# Main.net
KiCad netlist of a schematic drawn in Altium Designer
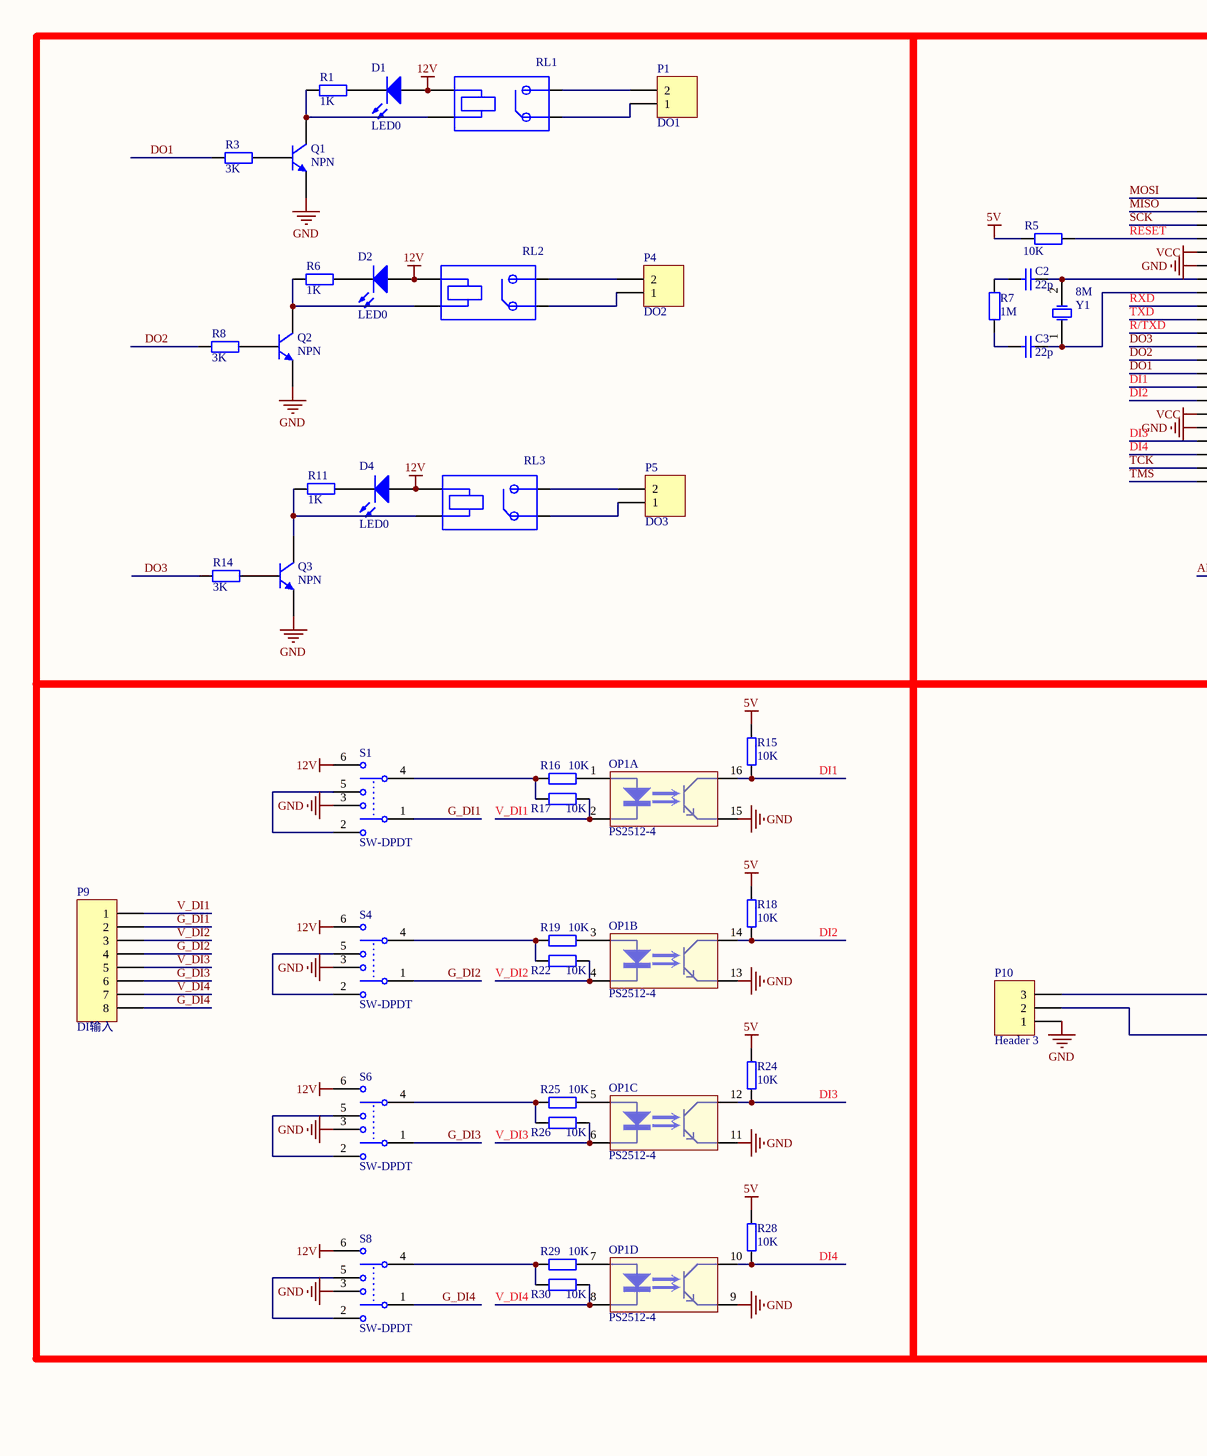
[diagram p0: Main.SchDoc, left]
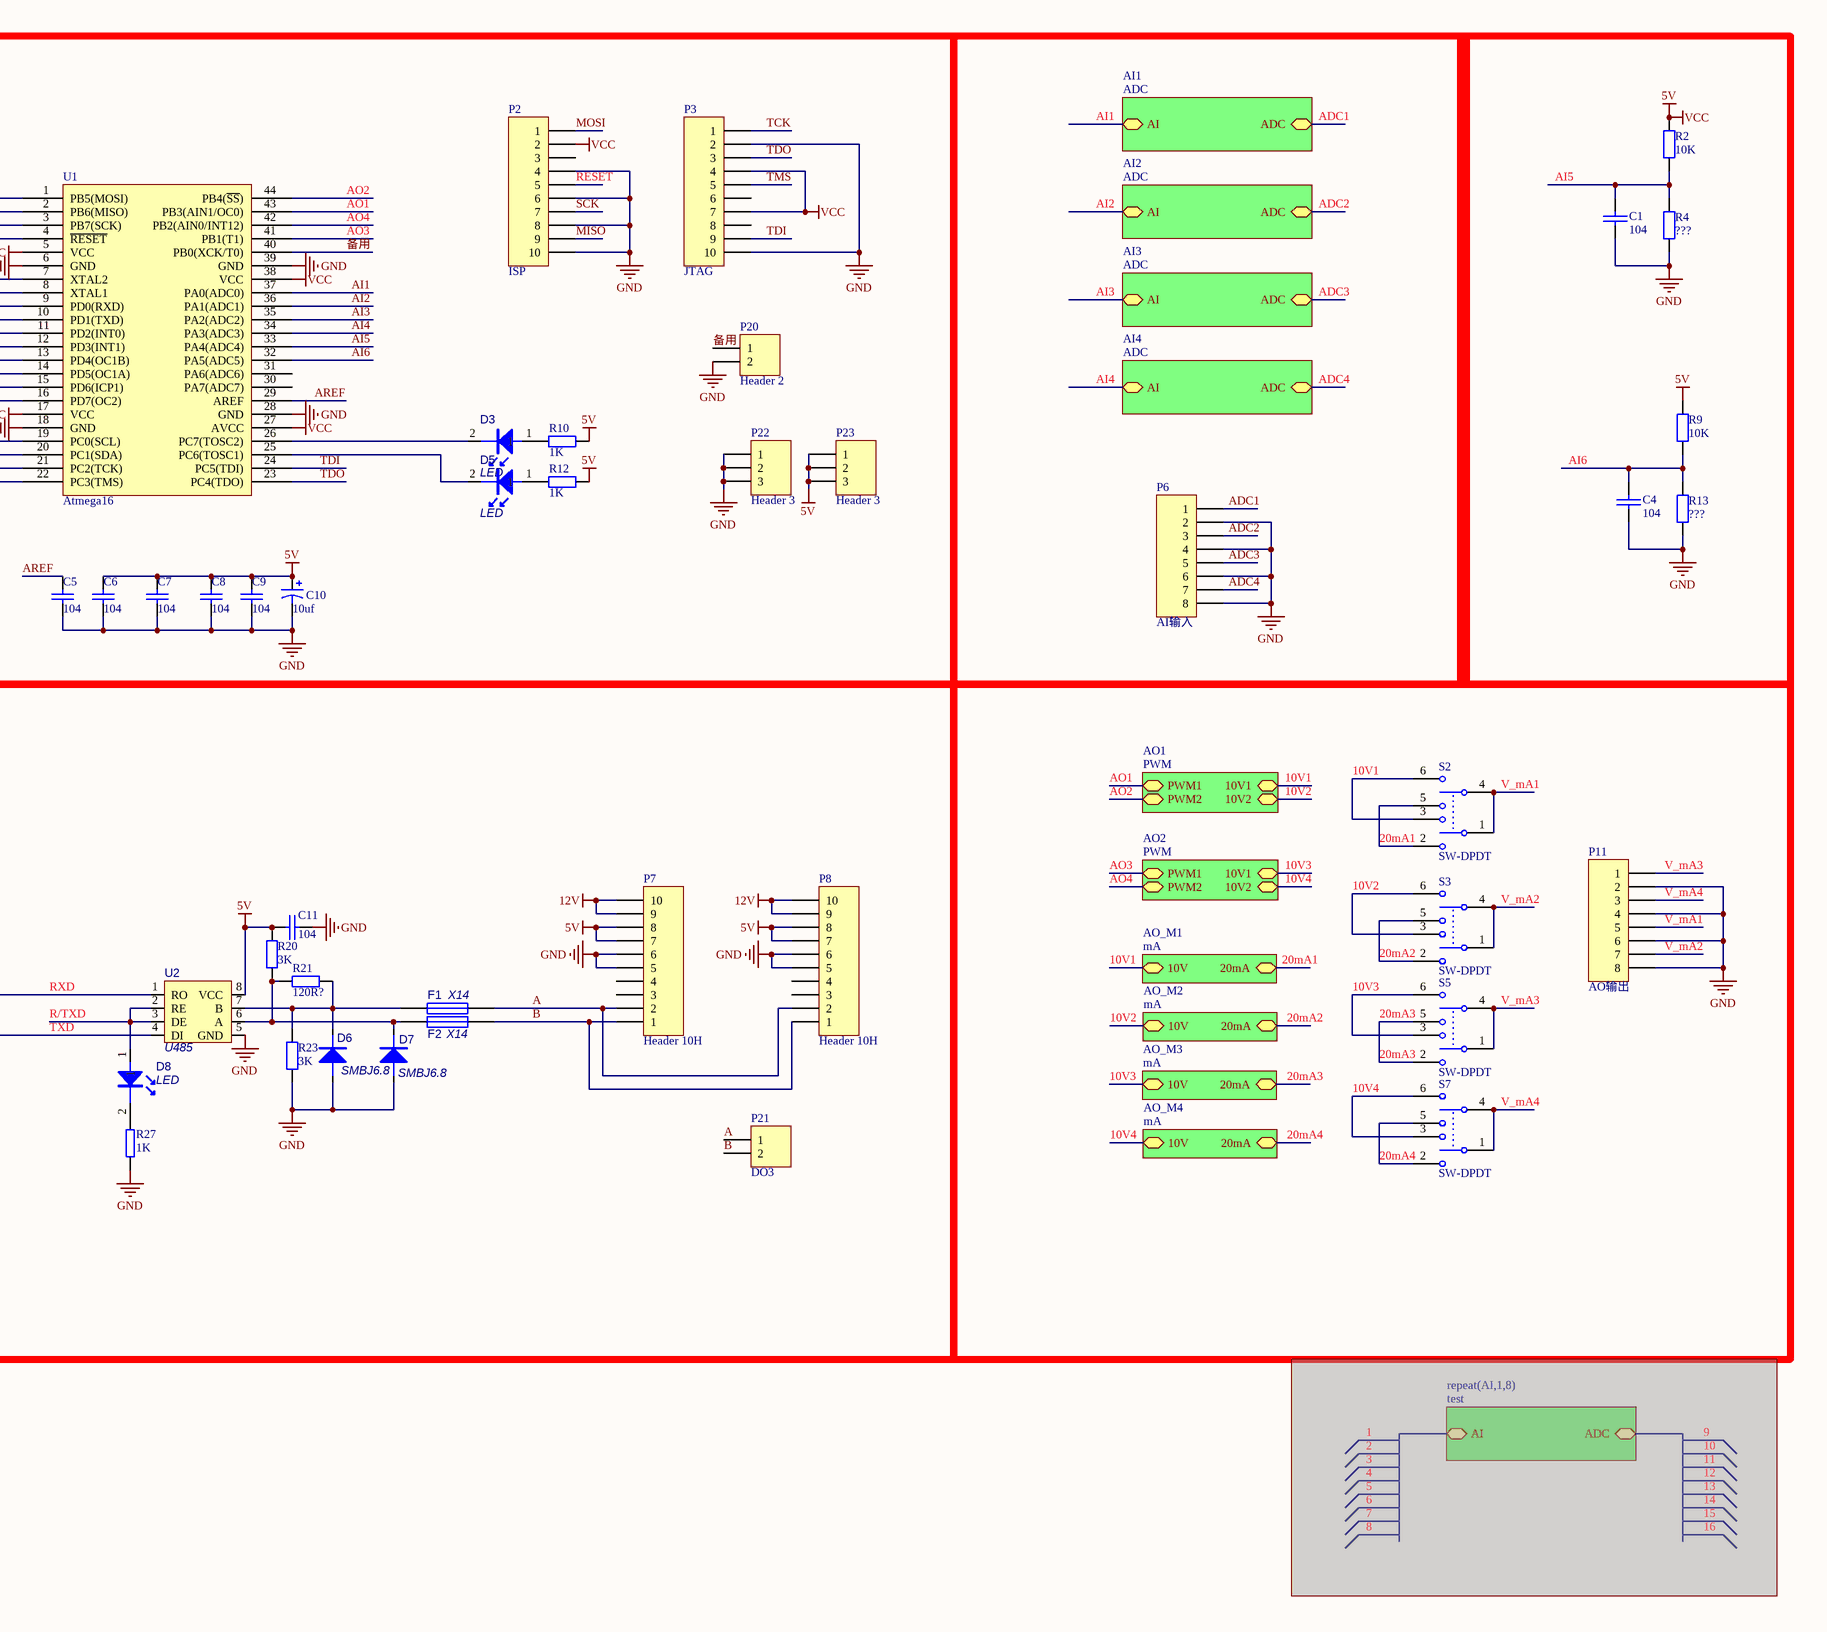
[diagram p1: Main.SchDoc, right]

(export (version "E")
  (design (tool "Eeschema 10.0.6"))
  (components
    (comp (ref "C1")
      (value "104")
      (footprint "C0805C")
      (description "Capacitor")
      (libsource (lib "*") (part "CAP"))
    )
    (comp (ref "C2")
      (value "22p")
      (footprint "c0805c")
      (description "Capacitor")
      (fields (field (name "PUBLISHER") "Altium Limited"))
      (libsource (lib "*") (part "Cap"))
    )
    (comp (ref "C3")
      (value "22p")
      (footprint "c0805c")
      (description "Capacitor")
      (fields (field (name "PUBLISHER") "Altium Limited"))
      (libsource (lib "*") (part "Cap"))
    )
    (comp (ref "C4")
      (value "104")
      (footprint "C0805C")
      (description "Capacitor")
      (libsource (lib "*") (part "CAP"))
    )
    (comp (ref "C5")
      (value "104")
      (footprint "c0805c")
      (description "Capacitor")
      (fields (field (name "PUBLISHER") "Altium Limited"))
      (libsource (lib "*") (part "Cap"))
    )
    (comp (ref "C6")
      (value "104")
      (footprint "c0805c")
      (description "Capacitor")
      (fields (field (name "PUBLISHER") "Altium Limited"))
      (libsource (lib "*") (part "Cap"))
    )
    (comp (ref "C7")
      (value "104")
      (footprint "c0805c")
      (description "Capacitor")
      (fields (field (name "PUBLISHER") "Altium Limited"))
      (libsource (lib "*") (part "Cap"))
    )
    (comp (ref "C8")
      (value "104")
      (footprint "c0805c")
      (description "Capacitor")
      (fields (field (name "PUBLISHER") "Altium Limited"))
      (libsource (lib "*") (part "Cap"))
    )
    (comp (ref "C9")
      (value "104")
      (footprint "c0805c")
      (description "Capacitor")
      (fields (field (name "PUBLISHER") "Altium Limited"))
      (libsource (lib "*") (part "Cap"))
    )
    (comp (ref "C10")
      (value "10uf")
      (footprint "E6.5MM")
      (description "Polarized Capacitor (Radial)")
      (fields (field (name "PUBLISHER") "Altium Limited"))
      (libsource (lib "PCB_Project1") (part "Cap Pol1"))
    )
    (comp (ref "C11")
      (value "104")
      (footprint "C0805C")
      (description "Capacitor")
      (libsource (lib "*") (part "CAP"))
    )
    (comp (ref "D1")
      (value "LED0")
      (footprint "LED0805")
      (description "Typical INFRARED GaAs LED")
      (fields (field (name "PUBLISHER") "Altium Limited"))
      (libsource (lib "Miscellaneous Devices") (part "LED0"))
    )
    (comp (ref "D2")
      (value "LED0")
      (footprint "LED0805")
      (description "Typical INFRARED GaAs LED")
      (fields (field (name "PUBLISHER") "Altium Limited"))
      (libsource (lib "Miscellaneous Devices") (part "LED0"))
    )
    (comp (ref "D3") (value "LED") (footprint "LED0805") (libsource (lib "*") (part "LED")))
    (comp (ref "D4")
      (value "LED0")
      (footprint "LED0805")
      (description "Typical INFRARED GaAs LED")
      (fields (field (name "PUBLISHER") "Altium Limited"))
      (libsource (lib "Miscellaneous Devices") (part "LED0"))
    )
    (comp (ref "D5") (value "LED") (footprint "LED0805") (libsource (lib "*") (part "LED")))
    (comp (ref "D6")
      (value "SMBJ6.8")
      (footprint "SMBJ_SMT")
      (description "Diode")
      (libsource (lib "*") (part "DIODE"))
    )
    (comp (ref "D7")
      (value "SMBJ6.8")
      (footprint "SMBJ_SMT")
      (description "Diode")
      (libsource (lib "*") (part "DIODE"))
    )
    (comp (ref "D8") (value "LED") (footprint "LED0805") (libsource (lib "*") (part "LED")))
    (comp (ref "F1")
      (value "X14")
      (footprint "PPTC_SMT")
      (description "Fuse")
      (fields (field (name "PUBLISHER") "Altium Limited"))
      (libsource (lib "Miscellaneous Devices") (part "Fuse 1"))
    )
    (comp (ref "F2")
      (value "X14")
      (footprint "PPTC_SMT")
      (description "Fuse")
      (fields (field (name "PUBLISHER") "Altium Limited"))
      (libsource (lib "Miscellaneous Devices") (part "Fuse 1"))
    )
    (comp (ref "OP1") (value "PS2512-4") (footprint "SO_16") (libsource (lib "POLx") (part "PS2512-4")))
    (comp (ref "P1")
      (value "DO1")
      (footprint "PL2Q")
      (description "Header, 2-Pin")
      (fields (field (name "PUBLISHER") "Altium Limited"))
      (libsource (lib "*") (part "Header 2"))
    )
    (comp (ref "P2")
      (value "ISP")
      (footprint "FC10")
      (description "Header, 10-Pin, Right Angle")
      (fields (field (name "PUBLISHER") "Altium Limited"))
      (libsource (lib "Miscellaneous Connectors") (part "Header 10H"))
    )
    (comp (ref "P3")
      (value "JTAG")
      (footprint "FC10P")
      (description "Header, 10-Pin, Right Angle")
      (fields (field (name "PUBLISHER") "Altium Limited"))
      (libsource (lib "Miscellaneous Connectors") (part "Header 10H"))
    )
    (comp (ref "P4")
      (value "DO2")
      (footprint "PL2Q")
      (description "Header, 2-Pin")
      (fields (field (name "PUBLISHER") "Altium Limited"))
      (libsource (lib "*") (part "Header 2"))
    )
    (comp (ref "P5")
      (value "DO3")
      (footprint "PL2Q")
      (description "Header, 2-Pin")
      (fields (field (name "PUBLISHER") "Altium Limited"))
      (libsource (lib "*") (part "Header 2"))
    )
    (comp (ref "P6")
      (value "AI输入")
      (footprint "8P _COM")
      (description "Header, 8-Pin")
      (fields (field (name "PUBLISHER") "Altium Limited"))
      (libsource (lib "Miscellaneous Connectors") (part "Header 8"))
    )
    (comp (ref "P7")
      (value "Header 10H")
      (footprint "FC10P_wan")
      (description "Header, 10-Pin, Right Angle")
      (fields (field (name "PUBLISHER") "Altium Limited"))
      (libsource (lib "") (part "Header 10H_1"))
    )
    (comp (ref "P8")
      (value "Header 10H")
      (footprint "FC10P_wan")
      (description "Header, 10-Pin, Right Angle")
      (fields (field (name "PUBLISHER") "Altium Limited"))
      (libsource (lib "") (part "Header 10H_1"))
    )
    (comp (ref "P9")
      (value "DI输入")
      (footprint "8P _COM")
      (description "Header, 8-Pin")
      (fields (field (name "PUBLISHER") "Altium Limited"))
      (libsource (lib "Miscellaneous Connectors") (part "Header 8"))
    )
    (comp (ref "P10")
      (value "Header 3")
      (footprint "HDR1X3")
      (description "Header, 3-Pin")
      (fields (field (name "PUBLISHER") "Altium Limited"))
      (libsource (lib "") (part "Header 3_1"))
    )
    (comp (ref "P11")
      (value "AO输出")
      (footprint "8P _COM")
      (description "Header, 8-Pin")
      (fields (field (name "PUBLISHER") "Altium Limited"))
      (libsource (lib "Miscellaneous Connectors") (part "Header 8"))
    )
    (comp (ref "P20")
      (value "Header 2")
      (footprint "HDR1X2")
      (description "Header, 2-Pin")
      (fields (field (name "PUBLISHER") "Altium Limited"))
      (libsource (lib "Miscellaneous Connectors") (part "Header 2"))
    )
    (comp (ref "P21")
      (value "DO3")
      (footprint "PL2Q")
      (description "Header, 2-Pin")
      (fields (field (name "PUBLISHER") "Altium Limited"))
      (libsource (lib "") (part "Header 2_1"))
    )
    (comp (ref "P22")
      (value "Header 3")
      (footprint "HDR1X3")
      (description "Header, 3-Pin")
      (fields (field (name "PUBLISHER") "Altium Limited"))
      (libsource (lib "Miscellaneous Connectors") (part "Header 3"))
    )
    (comp (ref "P23")
      (value "Header 3")
      (footprint "HDR1X3")
      (description "Header, 3-Pin")
      (fields (field (name "PUBLISHER") "Altium Limited"))
      (libsource (lib "Miscellaneous Connectors") (part "Header 3"))
    )
    (comp (ref "Q1")
      (value "NPN")
      (footprint "SOT23")
      (description "NPN Bipolar Transistor")
      (fields (field (name "PUBLISHER") "Altium Limited"))
      (libsource (lib "Miscellaneous Devices") (part "NPN"))
    )
    (comp (ref "Q2")
      (value "NPN")
      (footprint "SOT23")
      (description "NPN Bipolar Transistor")
      (fields (field (name "PUBLISHER") "Altium Limited"))
      (libsource (lib "Miscellaneous Devices") (part "NPN"))
    )
    (comp (ref "Q3")
      (value "NPN")
      (footprint "SOT23")
      (description "NPN Bipolar Transistor")
      (fields (field (name "PUBLISHER") "Altium Limited"))
      (libsource (lib "Miscellaneous Devices") (part "NPN"))
    )
    (comp (ref "R1")
      (value "1K")
      (footprint "0805R")
      (description "Resistor")
      (fields (field (name "PUBLISHER") "Altium Limited"))
      (libsource (lib "") (part "res_1"))
    )
    (comp (ref "R2")
      (value "10K")
      (footprint "0805R")
      (description "Resistor")
      (fields (field (name "PUBLISHER") "Altium Limited"))
      (libsource (lib "Miscellaneous Devices") (part "res"))
    )
    (comp (ref "R3")
      (value "3K")
      (footprint "0805R")
      (description "Resistor")
      (fields (field (name "PUBLISHER") "Altium Limited"))
      (libsource (lib "") (part "res_1"))
    )
    (comp (ref "R4")
      (value "???")
      (footprint "0805R")
      (description "Resistor")
      (fields (field (name "PUBLISHER") "Altium Limited"))
      (libsource (lib "Miscellaneous Devices") (part "res"))
    )
    (comp (ref "R5")
      (value "10K")
      (footprint "0805R")
      (description "Resistor")
      (fields (field (name "PUBLISHER") "Altium Limited"))
      (libsource (lib "") (part "res_1"))
    )
    (comp (ref "R6")
      (value "1K")
      (footprint "0805R")
      (description "Resistor")
      (fields (field (name "PUBLISHER") "Altium Limited"))
      (libsource (lib "") (part "res_1"))
    )
    (comp (ref "R7")
      (value "1M")
      (footprint "0805R")
      (description "Resistor")
      (fields (field (name "PUBLISHER") "Altium Limited"))
      (libsource (lib "") (part "res_2"))
    )
    (comp (ref "R8")
      (value "3K")
      (footprint "0805R")
      (description "Resistor")
      (fields (field (name "PUBLISHER") "Altium Limited"))
      (libsource (lib "") (part "res_1"))
    )
    (comp (ref "R9")
      (value "10K")
      (footprint "0805R")
      (description "Resistor")
      (fields (field (name "PUBLISHER") "Altium Limited"))
      (libsource (lib "Miscellaneous Devices") (part "res"))
    )
    (comp (ref "R10")
      (value "1K")
      (footprint "0805R")
      (description "Resistor")
      (fields (field (name "PUBLISHER") "Altium Limited"))
      (libsource (lib "") (part "res_1"))
    )
    (comp (ref "R11")
      (value "1K")
      (footprint "0805R")
      (description "Resistor")
      (fields (field (name "PUBLISHER") "Altium Limited"))
      (libsource (lib "") (part "res_1"))
    )
    (comp (ref "R12")
      (value "1K")
      (footprint "0805R")
      (description "Resistor")
      (fields (field (name "PUBLISHER") "Altium Limited"))
      (libsource (lib "") (part "res_1"))
    )
    (comp (ref "R13")
      (value "???")
      (footprint "0805R")
      (description "Resistor")
      (fields (field (name "PUBLISHER") "Altium Limited"))
      (libsource (lib "Miscellaneous Devices") (part "res"))
    )
    (comp (ref "R14")
      (value "3K")
      (footprint "0805R")
      (description "Resistor")
      (fields (field (name "PUBLISHER") "Altium Limited"))
      (libsource (lib "") (part "res_1"))
    )
    (comp (ref "R15") (value "10K") (footprint "0805R") (libsource (lib "*") (part "res")))
    (comp (ref "R16")
      (value "10K")
      (footprint "0805R")
      (description "Resistor")
      (fields (field (name "PUBLISHER") "Altium Limited"))
      (libsource (lib "Miscellaneous Devices") (part "res"))
    )
    (comp (ref "R17")
      (value "10K")
      (footprint "0805R")
      (description "Resistor")
      (fields (field (name "PUBLISHER") "Altium Limited"))
      (libsource (lib "Miscellaneous Devices") (part "res"))
    )
    (comp (ref "R18") (value "10K") (footprint "0805R") (libsource (lib "*") (part "res")))
    (comp (ref "R19")
      (value "10K")
      (footprint "0805R")
      (description "Resistor")
      (fields (field (name "PUBLISHER") "Altium Limited"))
      (libsource (lib "Miscellaneous Devices") (part "res"))
    )
    (comp (ref "R20")
      (value "3K")
      (footprint "0805R")
      (description "Resistor")
      (fields (field (name "PUBLISHER") "Altium Limited"))
      (libsource (lib "") (part "res_3"))
    )
    (comp (ref "R21")
      (value "120R?")
      (footprint "0805R")
      (description "Resistor")
      (fields (field (name "PUBLISHER") "Altium Limited"))
      (libsource (lib "Miscellaneous Devices") (part "res"))
    )
    (comp (ref "R22")
      (value "10K")
      (footprint "0805R")
      (description "Resistor")
      (fields (field (name "PUBLISHER") "Altium Limited"))
      (libsource (lib "Miscellaneous Devices") (part "res"))
    )
    (comp (ref "R23")
      (value "3K")
      (footprint "0805R")
      (description "Resistor")
      (fields (field (name "PUBLISHER") "Altium Limited"))
      (libsource (lib "") (part "res_3"))
    )
    (comp (ref "R24") (value "10K") (footprint "0805R") (libsource (lib "*") (part "res")))
    (comp (ref "R25")
      (value "10K")
      (footprint "0805R")
      (description "Resistor")
      (fields (field (name "PUBLISHER") "Altium Limited"))
      (libsource (lib "Miscellaneous Devices") (part "res"))
    )
    (comp (ref "R26")
      (value "10K")
      (footprint "0805R")
      (description "Resistor")
      (fields (field (name "PUBLISHER") "Altium Limited"))
      (libsource (lib "Miscellaneous Devices") (part "res"))
    )
    (comp (ref "R27") (value "1K") (footprint "0805R") (libsource (lib "*") (part "res")))
    (comp (ref "R28") (value "10K") (footprint "0805R") (libsource (lib "*") (part "res")))
    (comp (ref "R29")
      (value "10K")
      (footprint "0805R")
      (description "Resistor")
      (fields (field (name "PUBLISHER") "Altium Limited"))
      (libsource (lib "Miscellaneous Devices") (part "res"))
    )
    (comp (ref "R30")
      (value "10K")
      (footprint "0805R")
      (description "Resistor")
      (fields (field (name "PUBLISHER") "Altium Limited"))
      (libsource (lib "Miscellaneous Devices") (part "res"))
    )
    (comp (ref "RL1") (value "~") (footprint "HF32A4") (libsource (lib "*") (part "RELAY")))
    (comp (ref "RL2") (value "~") (footprint "HF32A4") (libsource (lib "*") (part "RELAY")))
    (comp (ref "RL3") (value "~") (footprint "HF32A4") (libsource (lib "*") (part "RELAY")))
    (comp (ref "S1")
      (value "SW-DPDT")
      (footprint "button")
      (description "Double-Pole, Double-Throw Switch")
      (fields (field (name "PUBLISHER") "Altium Limited"))
      (libsource (lib "Miscellaneous Devices") (part "SW-DPDT"))
    )
    (comp (ref "S2")
      (value "SW-DPDT")
      (footprint "button")
      (description "Double-Pole, Double-Throw Switch")
      (fields (field (name "PUBLISHER") "Altium Limited"))
      (libsource (lib "Miscellaneous Devices") (part "SW-DPDT"))
    )
    (comp (ref "S3")
      (value "SW-DPDT")
      (footprint "button")
      (description "Double-Pole, Double-Throw Switch")
      (fields (field (name "PUBLISHER") "Altium Limited"))
      (libsource (lib "Miscellaneous Devices") (part "SW-DPDT"))
    )
    (comp (ref "S4")
      (value "SW-DPDT")
      (footprint "button")
      (description "Double-Pole, Double-Throw Switch")
      (fields (field (name "PUBLISHER") "Altium Limited"))
      (libsource (lib "Miscellaneous Devices") (part "SW-DPDT"))
    )
    (comp (ref "S5")
      (value "SW-DPDT")
      (footprint "button")
      (description "Double-Pole, Double-Throw Switch")
      (fields (field (name "PUBLISHER") "Altium Limited"))
      (libsource (lib "Miscellaneous Devices") (part "SW-DPDT"))
    )
    (comp (ref "S6")
      (value "SW-DPDT")
      (footprint "button")
      (description "Double-Pole, Double-Throw Switch")
      (fields (field (name "PUBLISHER") "Altium Limited"))
      (libsource (lib "Miscellaneous Devices") (part "SW-DPDT"))
    )
    (comp (ref "S7")
      (value "SW-DPDT")
      (footprint "button")
      (description "Double-Pole, Double-Throw Switch")
      (fields (field (name "PUBLISHER") "Altium Limited"))
      (libsource (lib "Miscellaneous Devices") (part "SW-DPDT"))
    )
    (comp (ref "S8")
      (value "SW-DPDT")
      (footprint "button")
      (description "Double-Pole, Double-Throw Switch")
      (fields (field (name "PUBLISHER") "Altium Limited"))
      (libsource (lib "Miscellaneous Devices") (part "SW-DPDT"))
    )
    (comp (ref "U1")
      (value "Atmega16")
      (footprint "QFP44")
      (libsource (lib "CL_FS_A(V1.0)") (part "Atmega16"))
    )
    (comp (ref "U2") (value "U485") (footprint "SOP8") (libsource (lib "POL485") (part "U485")))
    (comp (ref "Y1")
      (value "8M")
      (footprint "XTAL-M")
      (description "Crystal Oscillator")
      (fields (field (name "PUBLISHER") "Altium Limited"))
      (libsource (lib "*") (part "XTAL"))
    )
  )
  (nets
    (net (code "11") (name "/10V1") (class "Default")
      (node (ref "S2") (pin "3") (pinfunction "3_3") (pintype "passive"))
      (node (ref "S2") (pin "6") (pinfunction "6_6") (pintype "passive"))
    )
    (net (code "12") (name "/10V2") (class "Default")
      (node (ref "S3") (pin "3") (pinfunction "3_3") (pintype "passive"))
      (node (ref "S3") (pin "6") (pinfunction "6_6") (pintype "passive"))
    )
    (net (code "13") (name "/10V3") (class "Default")
      (node (ref "S5") (pin "3") (pinfunction "3_3") (pintype "passive"))
      (node (ref "S5") (pin "6") (pinfunction "6_6") (pintype "passive"))
    )
    (net (code "14") (name "/10V4") (class "Default")
      (node (ref "S7") (pin "3") (pinfunction "3_3") (pintype "passive"))
      (node (ref "S7") (pin "6") (pinfunction "6_6") (pintype "passive"))
    )
    (net (code "21") (name "/20mA1") (class "Default")
      (node (ref "S2") (pin "2") (pinfunction "2_2") (pintype "passive"))
      (node (ref "S2") (pin "5") (pinfunction "5_5") (pintype "passive"))
    )
    (net (code "22") (name "/20mA2") (class "Default")
      (node (ref "S3") (pin "2") (pinfunction "2_2") (pintype "passive"))
      (node (ref "S3") (pin "5") (pinfunction "5_5") (pintype "passive"))
    )
    (net (code "23") (name "/20mA3") (class "Default")
      (node (ref "S5") (pin "2") (pinfunction "2_2") (pintype "passive"))
      (node (ref "S5") (pin "5") (pinfunction "5_5") (pintype "passive"))
    )
    (net (code "24") (name "/20mA4") (class "Default")
      (node (ref "S7") (pin "2") (pinfunction "2_2") (pintype "passive"))
      (node (ref "S7") (pin "5") (pinfunction "5_5") (pintype "passive"))
    )
    (net (code "25") (name "/A") (class "Default")
      (node (ref "F1") (pin "1") (pinfunction "1_1") (pintype "passive"))
      (node (ref "P21") (pin "1") (pinfunction "1_1") (pintype "passive"))
      (node (ref "P7") (pin "2") (pinfunction "2_2") (pintype "passive"))
      (node (ref "P8") (pin "2") (pinfunction "2_2") (pintype "passive"))
    )
    (net (code "27") (name "/ADC1") (class "Default")
      (node (ref "P6") (pin "1") (pinfunction "1_1") (pintype "passive"))
    )
    (net (code "28") (name "/ADC2") (class "Default")
      (node (ref "P6") (pin "3") (pinfunction "3_3") (pintype "passive"))
    )
    (net (code "29") (name "/ADC3") (class "Default")
      (node (ref "P6") (pin "5") (pinfunction "5_5") (pintype "passive"))
    )
    (net (code "30") (name "/ADC4") (class "Default")
      (node (ref "P6") (pin "7") (pinfunction "7_7") (pintype "passive"))
    )
    (net (code "32") (name "/AI1") (class "Default")
      (node (ref "U1") (pin "37") (pinfunction "PA0(ADC0)_37") (pintype "passive"))
    )
    (net (code "33") (name "/AI2") (class "Default")
      (node (ref "U1") (pin "36") (pinfunction "PA1(ADC1)_36") (pintype "passive"))
    )
    (net (code "34") (name "/AI3") (class "Default")
      (node (ref "U1") (pin "35") (pinfunction "PA2(ADC2)_35") (pintype "passive"))
    )
    (net (code "35") (name "/AI4") (class "Default")
      (node (ref "U1") (pin "34") (pinfunction "PA3(ADC3)_34") (pintype "passive"))
    )
    (net (code "36") (name "/AI5") (class "Default")
      (node (ref "C1") (pin "1") (pinfunction "1_1") (pintype "passive"))
      (node (ref "R2") (pin "1") (pinfunction "1_1") (pintype "passive"))
      (node (ref "R4") (pin "2") (pinfunction "2_2") (pintype "passive"))
      (node (ref "U1") (pin "33") (pinfunction "PA4(ADC4)_33") (pintype "passive"))
    )
    (net (code "37") (name "/AI6") (class "Default")
      (node (ref "C4") (pin "1") (pinfunction "1_1") (pintype "passive"))
      (node (ref "R13") (pin "2") (pinfunction "2_2") (pintype "passive"))
      (node (ref "R9") (pin "1") (pinfunction "1_1") (pintype "passive"))
      (node (ref "U1") (pin "32") (pinfunction "PA5(ADC5)_32") (pintype "passive"))
    )
    (net (code "38") (name "/AO1") (class "Default")
      (node (ref "U1") (pin "43") (pinfunction "PB3(AIN1/OC0)_43") (pintype "passive"))
    )
    (net (code "39") (name "/AO2") (class "Default")
      (node (ref "U1") (pin "44") (pinfunction "PB4(~{SS})_44") (pintype "passive"))
    )
    (net (code "40") (name "/AO3") (class "Default")
      (node (ref "U1") (pin "41") (pinfunction "PB1(T1)_41") (pintype "passive"))
    )
    (net (code "41") (name "/AO4") (class "Default")
      (node (ref "U1") (pin "42") (pinfunction "PB2(AIN0/INT12)_42") (pintype "passive"))
    )
    (net (code "42") (name "/AREF") (class "Default")
      (node (ref "C5") (pin "2") (pinfunction "2_2") (pintype "passive"))
      (node (ref "U1") (pin "29") (pinfunction "AREF_29") (pintype "passive"))
    )
    (net (code "43") (name "/B") (class "Default")
      (node (ref "F2") (pin "1") (pinfunction "1_1") (pintype "passive"))
      (node (ref "P21") (pin "2") (pinfunction "2_2") (pintype "passive"))
      (node (ref "P7") (pin "1") (pinfunction "1_1") (pintype "passive"))
      (node (ref "P8") (pin "1") (pinfunction "1_1") (pintype "passive"))
    )
    (net (code "44") (name "/DI1") (class "Default")
      (node (ref "OP1") (pin "16") (pinfunction "16_16") (pintype "passive"))
      (node (ref "R15") (pin "1") (pinfunction "1_1") (pintype "passive"))
      (node (ref "U1") (pin "15") (pinfunction "PD6(ICP1)_15") (pintype "passive"))
    )
    (net (code "45") (name "/DI2") (class "Default")
      (node (ref "OP1") (pin "14") (pinfunction "14_14") (pintype "passive"))
      (node (ref "R18") (pin "1") (pinfunction "1_1") (pintype "passive"))
      (node (ref "U1") (pin "16") (pinfunction "PD7(OC2)_16") (pintype "passive"))
    )
    (net (code "46") (name "/DI3") (class "Default")
      (node (ref "OP1") (pin "12") (pinfunction "12_12") (pintype "passive"))
      (node (ref "R24") (pin "1") (pinfunction "1_1") (pintype "passive"))
      (node (ref "U1") (pin "19") (pinfunction "PC0(SCL)_19") (pintype "passive"))
    )
    (net (code "47") (name "/DI4") (class "Default")
      (node (ref "OP1") (pin "10") (pinfunction "10_10") (pintype "passive"))
      (node (ref "R28") (pin "1") (pinfunction "1_1") (pintype "passive"))
      (node (ref "U1") (pin "20") (pinfunction "PC1(SDA)_20") (pintype "passive"))
    )
    (net (code "48") (name "/DO1") (class "Default")
      (node (ref "R3") (pin "2") (pinfunction "2_2") (pintype "passive"))
      (node (ref "U1") (pin "14") (pinfunction "PD5(OC1A)_14") (pintype "passive"))
    )
    (net (code "49") (name "/DO2") (class "Default")
      (node (ref "R8") (pin "2") (pinfunction "2_2") (pintype "passive"))
      (node (ref "U1") (pin "13") (pinfunction "PD4(OC1B)_13") (pintype "passive"))
    )
    (net (code "50") (name "/DO3") (class "Default")
      (node (ref "R14") (pin "2") (pinfunction "2_2") (pintype "passive"))
      (node (ref "U1") (pin "12") (pinfunction "PD3(INT1)_12") (pintype "passive"))
    )
    (net (code "51") (name "/G_DI1") (class "Default")
      (node (ref "P9") (pin "2") (pinfunction "2_2") (pintype "passive"))
      (node (ref "S1") (pin "1") (pinfunction "1_1") (pintype "passive"))
    )
    (net (code "52") (name "/G_DI2") (class "Default")
      (node (ref "P9") (pin "4") (pinfunction "4_4") (pintype "passive"))
      (node (ref "S4") (pin "1") (pinfunction "1_1") (pintype "passive"))
    )
    (net (code "53") (name "/G_DI3") (class "Default")
      (node (ref "P9") (pin "6") (pinfunction "6_6") (pintype "passive"))
      (node (ref "S6") (pin "1") (pinfunction "1_1") (pintype "passive"))
    )
    (net (code "54") (name "/G_DI4") (class "Default")
      (node (ref "P9") (pin "8") (pinfunction "8_8") (pintype "passive"))
      (node (ref "S8") (pin "1") (pinfunction "1_1") (pintype "passive"))
    )
    (net (code "55") (name "/MISO") (class "Default")
      (node (ref "P2") (pin "9") (pinfunction "9_9") (pintype "passive"))
      (node (ref "U1") (pin "2") (pinfunction "PB6(MISO)_2") (pintype "passive"))
    )
    (net (code "56") (name "/MOSI") (class "Default")
      (node (ref "P2") (pin "1") (pinfunction "1_1") (pintype "passive"))
      (node (ref "U1") (pin "1") (pinfunction "PB5(MOSI)_1") (pintype "passive"))
    )
    (net (code "57") (name "/RESET") (class "Default")
      (node (ref "P2") (pin "5") (pinfunction "5_5") (pintype "passive"))
      (node (ref "R5") (pin "1") (pinfunction "1_1") (pintype "passive"))
      (node (ref "U1") (pin "4") (pinfunction "~{RESET}_4") (pintype "passive"))
    )
    (net (code "58") (name "/RXD") (class "Default")
      (node (ref "P10") (pin "3") (pinfunction "3_3") (pintype "passive"))
      (node (ref "U1") (pin "9") (pinfunction "PD0(RXD)_9") (pintype "passive"))
      (node (ref "U2") (pin "1") (pinfunction "RO_1") (pintype "passive"))
    )
    (net (code "59") (name "/R{slash}TXD") (class "Default")
      (node (ref "D8") (pin "1") (pinfunction "1_1") (pintype "passive"))
      (node (ref "U1") (pin "11") (pinfunction "PD2(INT0)_11") (pintype "passive"))
      (node (ref "U2") (pin "2") (pinfunction "RE_2") (pintype "passive"))
      (node (ref "U2") (pin "3") (pinfunction "DE_3") (pintype "passive"))
    )
    (net (code "60") (name "/SCK") (class "Default")
      (node (ref "P2") (pin "7") (pinfunction "7_7") (pintype "passive"))
      (node (ref "U1") (pin "3") (pinfunction "PB7(SCK)_3") (pintype "passive"))
    )
    (net (code "61") (name "/TCK") (class "Default")
      (node (ref "P3") (pin "1") (pinfunction "1_1") (pintype "passive"))
      (node (ref "U1") (pin "21") (pinfunction "PC2(TCK)_21") (pintype "passive"))
    )
    (net (code "62") (name "/TDI") (class "Default")
      (node (ref "P3") (pin "9") (pinfunction "9_9") (pintype "passive"))
      (node (ref "U1") (pin "24") (pinfunction "PC5(TDI)_24") (pintype "passive"))
    )
    (net (code "63") (name "/TDO") (class "Default")
      (node (ref "P3") (pin "3") (pinfunction "3_3") (pintype "passive"))
      (node (ref "U1") (pin "23") (pinfunction "PC4(TDO)_23") (pintype "passive"))
    )
    (net (code "64") (name "/TMS") (class "Default")
      (node (ref "P3") (pin "5") (pinfunction "5_5") (pintype "passive"))
      (node (ref "U1") (pin "22") (pinfunction "PC3(TMS)_22") (pintype "passive"))
    )
    (net (code "65") (name "/TXD") (class "Default")
      (node (ref "P10") (pin "2") (pinfunction "2_2") (pintype "passive"))
      (node (ref "U1") (pin "10") (pinfunction "PD1(TXD)_10") (pintype "passive"))
      (node (ref "U2") (pin "4") (pinfunction "DI_4") (pintype "passive"))
    )
    (net (code "66") (name "/V_DI1") (class "Default")
      (node (ref "OP1") (pin "2") (pinfunction "2_2") (pintype "passive"))
      (node (ref "P9") (pin "1") (pinfunction "1_1") (pintype "passive"))
      (node (ref "R17") (pin "2") (pinfunction "2_2") (pintype "passive"))
    )
    (net (code "67") (name "/V_DI2") (class "Default")
      (node (ref "OP1") (pin "4") (pinfunction "4_4") (pintype "passive"))
      (node (ref "P9") (pin "3") (pinfunction "3_3") (pintype "passive"))
      (node (ref "R22") (pin "2") (pinfunction "2_2") (pintype "passive"))
    )
    (net (code "68") (name "/V_DI3") (class "Default")
      (node (ref "OP1") (pin "6") (pinfunction "6_6") (pintype "passive"))
      (node (ref "P9") (pin "5") (pinfunction "5_5") (pintype "passive"))
      (node (ref "R26") (pin "2") (pinfunction "2_2") (pintype "passive"))
    )
    (net (code "69") (name "/V_DI4") (class "Default")
      (node (ref "OP1") (pin "8") (pinfunction "8_8") (pintype "passive"))
      (node (ref "P9") (pin "7") (pinfunction "7_7") (pintype "passive"))
      (node (ref "R30") (pin "2") (pinfunction "2_2") (pintype "passive"))
    )
    (net (code "70") (name "/V_mA1") (class "Default")
      (node (ref "P11") (pin "5") (pinfunction "5_5") (pintype "passive"))
      (node (ref "S2") (pin "1") (pinfunction "1_1") (pintype "passive"))
      (node (ref "S2") (pin "4") (pinfunction "4_4") (pintype "passive"))
    )
    (net (code "71") (name "/V_mA2") (class "Default")
      (node (ref "P11") (pin "7") (pinfunction "7_7") (pintype "passive"))
      (node (ref "S3") (pin "1") (pinfunction "1_1") (pintype "passive"))
      (node (ref "S3") (pin "4") (pinfunction "4_4") (pintype "passive"))
    )
    (net (code "72") (name "/V_mA3") (class "Default")
      (node (ref "P11") (pin "1") (pinfunction "1_1") (pintype "passive"))
      (node (ref "S5") (pin "1") (pinfunction "1_1") (pintype "passive"))
      (node (ref "S5") (pin "4") (pinfunction "4_4") (pintype "passive"))
    )
    (net (code "73") (name "/V_mA4") (class "Default")
      (node (ref "P11") (pin "3") (pinfunction "3_3") (pintype "passive"))
      (node (ref "S7") (pin "1") (pinfunction "1_1") (pintype "passive"))
      (node (ref "S7") (pin "4") (pinfunction "4_4") (pintype "passive"))
    )
    (net (code "74") (name "/备用") (class "Default")
      (node (ref "P20") (pin "1") (pinfunction "1_1") (pintype "passive"))
      (node (ref "U1") (pin "40") (pinfunction "PB0(XCK/T0)_40") (pintype "passive"))
    )
    (net (code "75") (name "5V") (class "Default")
      (node (ref "C10") (pin "1") (pinfunction "1_1") (pintype "passive"))
      (node (ref "C11") (pin "1") (pinfunction "1_1") (pintype "passive"))
      (node (ref "C6") (pin "2") (pinfunction "2_2") (pintype "passive"))
      (node (ref "C7") (pin "2") (pinfunction "2_2") (pintype "passive"))
      (node (ref "C8") (pin "2") (pinfunction "2_2") (pintype "passive"))
      (node (ref "C9") (pin "1") (pinfunction "1_1") (pintype "passive"))
      (node (ref "P2") (pin "2") (pinfunction "2_2") (pintype "passive"))
      (node (ref "P23") (pin "1") (pinfunction "1_1") (pintype "passive"))
      (node (ref "P23") (pin "2") (pinfunction "2_2") (pintype "passive"))
      (node (ref "P23") (pin "3") (pinfunction "3_3") (pintype "passive"))
      (node (ref "P3") (pin "4") (pinfunction "4_4") (pintype "passive"))
      (node (ref "P3") (pin "7") (pinfunction "7_7") (pintype "passive"))
      (node (ref "P7") (pin "7") (pinfunction "7_7") (pintype "passive"))
      (node (ref "P7") (pin "8") (pinfunction "8_8") (pintype "passive"))
      (node (ref "P8") (pin "7") (pinfunction "7_7") (pintype "passive"))
      (node (ref "P8") (pin "8") (pinfunction "8_8") (pintype "passive"))
      (node (ref "R10") (pin "1") (pinfunction "1_1") (pintype "passive"))
      (node (ref "R12") (pin "1") (pinfunction "1_1") (pintype "passive"))
      (node (ref "R15") (pin "2") (pinfunction "0_2") (pintype "passive"))
      (node (ref "R18") (pin "2") (pinfunction "0_2") (pintype "passive"))
      (node (ref "R2") (pin "2") (pinfunction "2_2") (pintype "passive"))
      (node (ref "R20") (pin "2") (pinfunction "2_2") (pintype "passive"))
      (node (ref "R24") (pin "2") (pinfunction "0_2") (pintype "passive"))
      (node (ref "R28") (pin "2") (pinfunction "0_2") (pintype "passive"))
      (node (ref "R5") (pin "2") (pinfunction "2_2") (pintype "passive"))
      (node (ref "R9") (pin "2") (pinfunction "2_2") (pintype "passive"))
      (node (ref "U1") (pin "17") (pinfunction "VCC_17") (pintype "passive"))
      (node (ref "U1") (pin "27") (pinfunction "AVCC_27") (pintype "passive"))
      (node (ref "U1") (pin "38") (pinfunction "VCC_38") (pintype "passive"))
      (node (ref "U1") (pin "5") (pinfunction "VCC_5") (pintype "passive"))
      (node (ref "U2") (pin "8") (pinfunction "VCC_8") (pintype "passive"))
    )
    (net (code "76") (name "12V") (class "Default")
      (node (ref "D1") (pin "1") (pinfunction "A_1") (pintype "passive"))
      (node (ref "D2") (pin "1") (pinfunction "A_1") (pintype "passive"))
      (node (ref "D4") (pin "1") (pinfunction "A_1") (pintype "passive"))
      (node (ref "P7") (pin "10") (pinfunction "10_10") (pintype "passive"))
      (node (ref "P7") (pin "9") (pinfunction "9_9") (pintype "passive"))
      (node (ref "P8") (pin "10") (pinfunction "10_10") (pintype "passive"))
      (node (ref "P8") (pin "9") (pinfunction "9_9") (pintype "passive"))
      (node (ref "RL1") (pin "1") (pinfunction "1_1") (pintype "passive"))
      (node (ref "RL2") (pin "1") (pinfunction "1_1") (pintype "passive"))
      (node (ref "RL3") (pin "1") (pinfunction "1_1") (pintype "passive"))
      (node (ref "S1") (pin "6") (pinfunction "6_6") (pintype "passive"))
      (node (ref "S4") (pin "6") (pinfunction "6_6") (pintype "passive"))
      (node (ref "S6") (pin "6") (pinfunction "6_6") (pintype "passive"))
      (node (ref "S8") (pin "6") (pinfunction "6_6") (pintype "passive"))
    )
    (net (code "77") (name "GND") (class "Default")
      (node (ref "C1") (pin "2") (pinfunction "2_2") (pintype "passive"))
      (node (ref "C10") (pin "2") (pinfunction "2_2") (pintype "passive"))
      (node (ref "C11") (pin "2") (pinfunction "2_2") (pintype "passive"))
      (node (ref "C4") (pin "2") (pinfunction "2_2") (pintype "passive"))
      (node (ref "C5") (pin "1") (pinfunction "1_1") (pintype "passive"))
      (node (ref "C6") (pin "1") (pinfunction "1_1") (pintype "passive"))
      (node (ref "C7") (pin "1") (pinfunction "1_1") (pintype "passive"))
      (node (ref "C8") (pin "1") (pinfunction "1_1") (pintype "passive"))
      (node (ref "C9") (pin "2") (pinfunction "2_2") (pintype "passive"))
      (node (ref "D6") (pin "A") (pinfunction "A_A") (pintype "passive"))
      (node (ref "D7") (pin "A") (pinfunction "A_A") (pintype "passive"))
      (node (ref "OP1") (pin "11") (pinfunction "11_11") (pintype "passive"))
      (node (ref "OP1") (pin "13") (pinfunction "13_13") (pintype "passive"))
      (node (ref "OP1") (pin "15") (pinfunction "15_15") (pintype "passive"))
      (node (ref "OP1") (pin "9") (pinfunction "9_9") (pintype "passive"))
      (node (ref "P10") (pin "1") (pinfunction "1_1") (pintype "passive"))
      (node (ref "P11") (pin "2") (pinfunction "2_2") (pintype "passive"))
      (node (ref "P11") (pin "4") (pinfunction "4_4") (pintype "passive"))
      (node (ref "P11") (pin "6") (pinfunction "6_6") (pintype "passive"))
      (node (ref "P11") (pin "8") (pinfunction "8_8") (pintype "passive"))
      (node (ref "P2") (pin "10") (pinfunction "10_10") (pintype "passive"))
      (node (ref "P2") (pin "4") (pinfunction "4_4") (pintype "passive"))
      (node (ref "P2") (pin "6") (pinfunction "6_6") (pintype "passive"))
      (node (ref "P2") (pin "8") (pinfunction "8_8") (pintype "passive"))
      (node (ref "P20") (pin "2") (pinfunction "2_2") (pintype "passive"))
      (node (ref "P22") (pin "1") (pinfunction "1_1") (pintype "passive"))
      (node (ref "P22") (pin "2") (pinfunction "2_2") (pintype "passive"))
      (node (ref "P22") (pin "3") (pinfunction "3_3") (pintype "passive"))
      (node (ref "P3") (pin "10") (pinfunction "10_10") (pintype "passive"))
      (node (ref "P3") (pin "2") (pinfunction "2_2") (pintype "passive"))
      (node (ref "P6") (pin "2") (pinfunction "2_2") (pintype "passive"))
      (node (ref "P6") (pin "4") (pinfunction "4_4") (pintype "passive"))
      (node (ref "P6") (pin "6") (pinfunction "6_6") (pintype "passive"))
      (node (ref "P6") (pin "8") (pinfunction "8_8") (pintype "passive"))
      (node (ref "P7") (pin "5") (pinfunction "5_5") (pintype "passive"))
      (node (ref "P7") (pin "6") (pinfunction "6_6") (pintype "passive"))
      (node (ref "P8") (pin "5") (pinfunction "5_5") (pintype "passive"))
      (node (ref "P8") (pin "6") (pinfunction "6_6") (pintype "passive"))
      (node (ref "Q1") (pin "3") (pinfunction "E_3") (pintype "passive"))
      (node (ref "Q2") (pin "3") (pinfunction "E_3") (pintype "passive"))
      (node (ref "Q3") (pin "3") (pinfunction "E_3") (pintype "passive"))
      (node (ref "R13") (pin "1") (pinfunction "1_1") (pintype "passive"))
      (node (ref "R23") (pin "1") (pinfunction "1_1") (pintype "passive"))
      (node (ref "R27") (pin "1") (pinfunction "1_1") (pintype "passive"))
      (node (ref "R4") (pin "1") (pinfunction "1_1") (pintype "passive"))
      (node (ref "S1") (pin "3") (pinfunction "3_3") (pintype "passive"))
      (node (ref "S4") (pin "3") (pinfunction "3_3") (pintype "passive"))
      (node (ref "S6") (pin "3") (pinfunction "3_3") (pintype "passive"))
      (node (ref "S8") (pin "3") (pinfunction "3_3") (pintype "passive"))
      (node (ref "U1") (pin "18") (pinfunction "GND_18") (pintype "passive"))
      (node (ref "U1") (pin "28") (pinfunction "GND_28") (pintype "passive"))
      (node (ref "U1") (pin "39") (pinfunction "GND_39") (pintype "passive"))
      (node (ref "U1") (pin "6") (pinfunction "GND_6") (pintype "passive"))
      (node (ref "U2") (pin "5") (pinfunction "GND_5") (pintype "passive"))
    )
    (net (code "78") (name "Net-(C2-Pad2)") (class "Default")
      (node (ref "C2") (pin "2") (pinfunction "2_2") (pintype "passive"))
      (node (ref "R7") (pin "1") (pinfunction "1_1") (pintype "passive"))
    )
    (net (code "79") (name "Net-(C3-Pad2)") (class "Default")
      (node (ref "C3") (pin "2") (pinfunction "2_2") (pintype "passive"))
      (node (ref "R7") (pin "2") (pinfunction "2_2") (pintype "passive"))
    )
    (net (code "80") (name "Net-(D1-K)") (class "Default")
      (node (ref "D1") (pin "2") (pinfunction "K_2") (pintype "passive"))
      (node (ref "R1") (pin "1") (pinfunction "1_1") (pintype "passive"))
    )
    (net (code "81") (name "Net-(D2-K)") (class "Default")
      (node (ref "D2") (pin "2") (pinfunction "K_2") (pintype "passive"))
      (node (ref "R6") (pin "1") (pinfunction "1_1") (pintype "passive"))
    )
    (net (code "82") (name "Net-(D3-Pad1)") (class "Default")
      (node (ref "D3") (pin "1") (pinfunction "1_1") (pintype "passive"))
      (node (ref "R10") (pin "2") (pinfunction "2_2") (pintype "passive"))
    )
    (net (code "83") (name "Net-(D4-K)") (class "Default")
      (node (ref "D4") (pin "2") (pinfunction "K_2") (pintype "passive"))
      (node (ref "R11") (pin "1") (pinfunction "1_1") (pintype "passive"))
    )
    (net (code "84") (name "Net-(D5-Pad1)") (class "Default")
      (node (ref "D5") (pin "1") (pinfunction "1_1") (pintype "passive"))
      (node (ref "R12") (pin "2") (pinfunction "2_2") (pintype "passive"))
    )
    (net (code "85") (name "Net-(OP1-Pad1)") (class "Default")
      (node (ref "OP1") (pin "1") (pinfunction "1_1") (pintype "passive"))
      (node (ref "R16") (pin "2") (pinfunction "2_2") (pintype "passive"))
    )
    (net (code "86") (name "Net-(OP1-Pad3)") (class "Default")
      (node (ref "OP1") (pin "3") (pinfunction "3_3") (pintype "passive"))
      (node (ref "R19") (pin "2") (pinfunction "2_2") (pintype "passive"))
    )
    (net (code "87") (name "Net-(OP1-Pad5)") (class "Default")
      (node (ref "OP1") (pin "5") (pinfunction "5_5") (pintype "passive"))
      (node (ref "R25") (pin "2") (pinfunction "2_2") (pintype "passive"))
    )
    (net (code "88") (name "Net-(OP1-Pad7)") (class "Default")
      (node (ref "OP1") (pin "7") (pinfunction "7_7") (pintype "passive"))
      (node (ref "R29") (pin "2") (pinfunction "2_2") (pintype "passive"))
    )
    (net (code "89") (name "Net-(P1-Pad1)") (class "Default")
      (node (ref "P1") (pin "1") (pinfunction "1_1") (pintype "passive"))
      (node (ref "RL1") (pin "4") (pinfunction "4_4") (pintype "passive"))
    )
    (net (code "90") (name "Net-(P1-Pad2)") (class "Default")
      (node (ref "P1") (pin "2") (pinfunction "2_2") (pintype "passive"))
      (node (ref "RL1") (pin "3") (pinfunction "3_3") (pintype "passive"))
    )
    (net (code "91") (name "Net-(P4-Pad1)") (class "Default")
      (node (ref "P4") (pin "1") (pinfunction "1_1") (pintype "passive"))
      (node (ref "RL2") (pin "4") (pinfunction "4_4") (pintype "passive"))
    )
    (net (code "92") (name "Net-(P4-Pad2)") (class "Default")
      (node (ref "P4") (pin "2") (pinfunction "2_2") (pintype "passive"))
      (node (ref "RL2") (pin "3") (pinfunction "3_3") (pintype "passive"))
    )
    (net (code "93") (name "Net-(P5-Pad1)") (class "Default")
      (node (ref "P5") (pin "1") (pinfunction "1_1") (pintype "passive"))
      (node (ref "RL3") (pin "4") (pinfunction "4_4") (pintype "passive"))
    )
    (net (code "94") (name "Net-(P5-Pad2)") (class "Default")
      (node (ref "P5") (pin "2") (pinfunction "2_2") (pintype "passive"))
      (node (ref "RL3") (pin "3") (pinfunction "3_3") (pintype "passive"))
    )
    (net (code "95") (name "Net-(Q1-B)") (class "Default")
      (node (ref "Q1") (pin "2") (pinfunction "B_2") (pintype "passive"))
      (node (ref "R3") (pin "1") (pinfunction "1_1") (pintype "passive"))
    )
    (net (code "96") (name "Net-(Q1-C)") (class "Default")
      (node (ref "Q1") (pin "1") (pinfunction "C_1") (pintype "passive"))
      (node (ref "R1") (pin "2") (pinfunction "2_2") (pintype "passive"))
      (node (ref "RL1") (pin "2") (pinfunction "2_2") (pintype "passive"))
    )
    (net (code "97") (name "Net-(Q2-B)") (class "Default")
      (node (ref "Q2") (pin "2") (pinfunction "B_2") (pintype "passive"))
      (node (ref "R8") (pin "1") (pinfunction "1_1") (pintype "passive"))
    )
    (net (code "98") (name "Net-(Q2-C)") (class "Default")
      (node (ref "Q2") (pin "1") (pinfunction "C_1") (pintype "passive"))
      (node (ref "R6") (pin "2") (pinfunction "2_2") (pintype "passive"))
      (node (ref "RL2") (pin "2") (pinfunction "2_2") (pintype "passive"))
    )
    (net (code "99") (name "Net-(Q3-B)") (class "Default")
      (node (ref "Q3") (pin "2") (pinfunction "B_2") (pintype "passive"))
      (node (ref "R14") (pin "1") (pinfunction "1_1") (pintype "passive"))
    )
    (net (code "100") (name "Net-(Q3-C)") (class "Default")
      (node (ref "Q3") (pin "1") (pinfunction "C_1") (pintype "passive"))
      (node (ref "R11") (pin "2") (pinfunction "2_2") (pintype "passive"))
      (node (ref "RL3") (pin "2") (pinfunction "2_2") (pintype "passive"))
    )
    (net (code "101") (name "Net-(R16-Pad1)") (class "Default")
      (node (ref "R16") (pin "1") (pinfunction "1_1") (pintype "passive"))
      (node (ref "R17") (pin "1") (pinfunction "1_1") (pintype "passive"))
      (node (ref "S1") (pin "4") (pinfunction "4_4") (pintype "passive"))
    )
    (net (code "102") (name "Net-(R19-Pad1)") (class "Default")
      (node (ref "R19") (pin "1") (pinfunction "1_1") (pintype "passive"))
      (node (ref "R22") (pin "1") (pinfunction "1_1") (pintype "passive"))
      (node (ref "S4") (pin "4") (pinfunction "4_4") (pintype "passive"))
    )
    (net (code "103") (name "Net-(R25-Pad1)") (class "Default")
      (node (ref "R25") (pin "1") (pinfunction "1_1") (pintype "passive"))
      (node (ref "R26") (pin "1") (pinfunction "1_1") (pintype "passive"))
      (node (ref "S6") (pin "4") (pinfunction "4_4") (pintype "passive"))
    )
    (net (code "104") (name "Net-(R27-0)") (class "Default")
      (node (ref "D8") (pin "2") (pinfunction "2_2") (pintype "passive"))
      (node (ref "R27") (pin "2") (pinfunction "0_2") (pintype "passive"))
    )
    (net (code "105") (name "Net-(R29-Pad1)") (class "Default")
      (node (ref "R29") (pin "1") (pinfunction "1_1") (pintype "passive"))
      (node (ref "R30") (pin "1") (pinfunction "1_1") (pintype "passive"))
      (node (ref "S8") (pin "4") (pinfunction "4_4") (pintype "passive"))
    )
    (net (code "106") (name "Net-(S1-Pad2)") (class "Default")
      (node (ref "S1") (pin "2") (pinfunction "2_2") (pintype "passive"))
      (node (ref "S1") (pin "5") (pinfunction "5_5") (pintype "passive"))
    )
    (net (code "107") (name "Net-(S4-Pad2)") (class "Default")
      (node (ref "S4") (pin "2") (pinfunction "2_2") (pintype "passive"))
      (node (ref "S4") (pin "5") (pinfunction "5_5") (pintype "passive"))
    )
    (net (code "108") (name "Net-(S6-Pad2)") (class "Default")
      (node (ref "S6") (pin "2") (pinfunction "2_2") (pintype "passive"))
      (node (ref "S6") (pin "5") (pinfunction "5_5") (pintype "passive"))
    )
    (net (code "109") (name "Net-(S8-Pad2)") (class "Default")
      (node (ref "S8") (pin "2") (pinfunction "2_2") (pintype "passive"))
      (node (ref "S8") (pin "5") (pinfunction "5_5") (pintype "passive"))
    )
    (net (code "110") (name "Net-(U1-PC6(TOSC1))") (class "Default")
      (node (ref "D5") (pin "2") (pinfunction "2_2") (pintype "passive"))
      (node (ref "U1") (pin "25") (pinfunction "PC6(TOSC1)_25") (pintype "passive"))
    )
    (net (code "111") (name "Net-(U1-PC7(TOSC2))") (class "Default")
      (node (ref "D3") (pin "2") (pinfunction "2_2") (pintype "passive"))
      (node (ref "U1") (pin "26") (pinfunction "PC7(TOSC2)_26") (pintype "passive"))
    )
    (net (code "112") (name "Net-(U1-XTAL1)") (class "Default")
      (node (ref "C3") (pin "1") (pinfunction "1_1") (pintype "passive"))
      (node (ref "U1") (pin "8") (pinfunction "XTAL1_8") (pintype "passive"))
      (node (ref "Y1") (pin "1") (pinfunction "OSC1_1") (pintype "passive"))
    )
    (net (code "113") (name "Net-(U1-XTAL2)") (class "Default")
      (node (ref "C2") (pin "1") (pinfunction "1_1") (pintype "passive"))
      (node (ref "U1") (pin "7") (pinfunction "XTAL2_7") (pintype "passive"))
      (node (ref "Y1") (pin "2") (pinfunction "OSC2_2") (pintype "passive"))
    )
    (net (code "114") (name "Net-(U2-A)") (class "Default")
      (node (ref "D7") (pin "K") (pinfunction "K_K") (pintype "passive"))
      (node (ref "F2") (pin "2") (pinfunction "2_2") (pintype "passive"))
      (node (ref "R20") (pin "1") (pinfunction "1_1") (pintype "passive"))
      (node (ref "R21") (pin "1") (pinfunction "1_1") (pintype "passive"))
      (node (ref "U2") (pin "6") (pinfunction "A_6") (pintype "passive"))
    )
    (net (code "115") (name "Net-(U2-B)") (class "Default")
      (node (ref "D6") (pin "K") (pinfunction "K_K") (pintype "passive"))
      (node (ref "F1") (pin "2") (pinfunction "2_2") (pintype "passive"))
      (node (ref "R21") (pin "2") (pinfunction "2_2") (pintype "passive"))
      (node (ref "R23") (pin "2") (pinfunction "2_2") (pintype "passive"))
      (node (ref "U2") (pin "7") (pinfunction "B_7") (pintype "passive"))
    )
    (net (code "116") (name "unconnected-(P2-Pad3)") (class "Default")
      (node (ref "P2") (pin "3") (pinfunction "3_3") (pintype "passive"))
    )
    (net (code "117") (name "unconnected-(P3-Pad6)") (class "Default")
      (node (ref "P3") (pin "6") (pinfunction "6_6") (pintype "passive"))
    )
    (net (code "118") (name "unconnected-(P3-Pad8)") (class "Default")
      (node (ref "P3") (pin "8") (pinfunction "8_8") (pintype "passive"))
    )
    (net (code "119") (name "unconnected-(P7-Pad3)") (class "Default")
      (node (ref "P7") (pin "3") (pinfunction "3_3") (pintype "passive"))
    )
    (net (code "120") (name "unconnected-(P7-Pad4)") (class "Default")
      (node (ref "P7") (pin "4") (pinfunction "4_4") (pintype "passive"))
    )
    (net (code "121") (name "unconnected-(P8-Pad3)") (class "Default")
      (node (ref "P8") (pin "3") (pinfunction "3_3") (pintype "passive"))
    )
    (net (code "122") (name "unconnected-(P8-Pad4)") (class "Default")
      (node (ref "P8") (pin "4") (pinfunction "4_4") (pintype "passive"))
    )
    (net (code "123") (name "unconnected-(U1-PA6(ADC6)-Pad31)") (class "Default")
      (node (ref "U1") (pin "31") (pinfunction "PA6(ADC6)_31") (pintype "passive"))
    )
    (net (code "124") (name "unconnected-(U1-PA7(ADC7)-Pad30)") (class "Default")
      (node (ref "U1") (pin "30") (pinfunction "PA7(ADC7)_30") (pintype "passive"))
    )
  )
)
